# Eagle.net
KiCad netlist of a schematic drawn in EAGLE
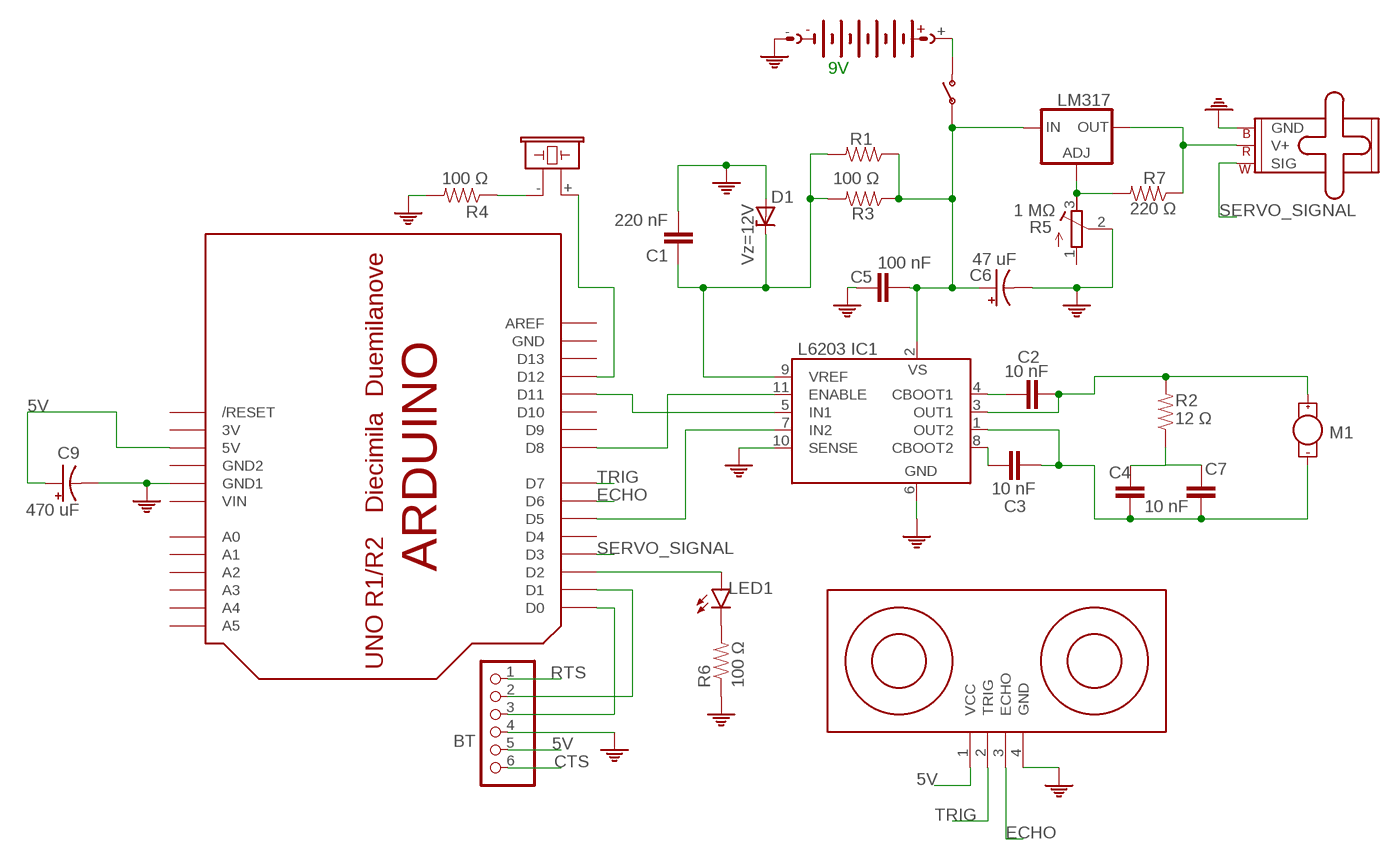
[diagram p0: schematic, sheet 1]

(export (version "E")
  (design (tool "Eeschema 10.0.6"))
  (components
    (comp (ref "9V")
      (value "9V")
      (footprint "eagle-import:AB9V")
      (libsource (lib "eagle-import") (part "AB9V"))
    )
    (comp (ref "BT")
      (value "PINHD-1X6")
      (footprint "eagle-import:1X06")
      (libsource (lib "eagle-import") (part "PINHD-1X6"))
    )
    (comp (ref "C1")
      (value "220 nF")
      (footprint "eagle-import:CAP-PTH-SMALLEZ")
      (libsource (lib "eagle-import") (part "CAPEZ"))
    )
    (comp (ref "C2")
      (value "10 nF")
      (footprint "eagle-import:CAP-PTH-SMALLEZ")
      (libsource (lib "eagle-import") (part "CAPEZ"))
    )
    (comp (ref "C3")
      (value "10 nF")
      (footprint "eagle-import:CAP-PTH-SMALLEZ")
      (libsource (lib "eagle-import") (part "CAPEZ"))
    )
    (comp (ref "C4")
      (value "10 nF")
      (footprint "eagle-import:CAP-PTH-SMALLEZ")
      (libsource (lib "eagle-import") (part "CAPEZ"))
    )
    (comp (ref "C5")
      (value "100 nF")
      (footprint "eagle-import:CAP-PTH-SMALLEZ")
      (libsource (lib "eagle-import") (part "CAPEZ"))
    )
    (comp (ref "C6")
      (value "47 uF")
      (footprint "eagle-import:E5-4")
      (libsource (lib "eagle-import") (part "CPOL-USE5-4"))
    )
    (comp (ref "C7")
      (value "10 nF")
      (footprint "eagle-import:CAP-PTH-SMALLEZ")
      (libsource (lib "eagle-import") (part "CAPEZ"))
    )
    (comp (ref "C9")
      (value "470 uF")
      (footprint "eagle-import:B45181A")
      (libsource (lib "eagle-import") (part "resistor_CPOL-USB45181A"))
    )
    (comp (ref "D1")
      (value "Vz=12V")
      (footprint "eagle-import:C1702-15")
      (libsource (lib "eagle-import") (part "ZENER-DIODEC1702-15"))
    )
    (comp (ref "IC1")
      (value "L6203")
      (footprint "eagle-import:MULTIWATT-11")
      (libsource (lib "eagle-import") (part "L6203"))
    )
    (comp (ref "LED1")
      (value "LED1")
      (footprint "eagle-import:LED3MM-NS")
      (libsource (lib "eagle-import") (part "LED-3MM-NO_SILK"))
    )
    (comp (ref "LM317")
      (value "LM317TS")
      (footprint "eagle-import:317TS")
      (libsource (lib "eagle-import") (part "LM317TS"))
    )
    (comp (ref "M1")
      (value "MOTOR10MM")
      (footprint "eagle-import:VIBE-MOTOR-10MM")
      (libsource (lib "eagle-import") (part "MOTOR10MM"))
    )
    (comp (ref "M2")
      (value "SMALL_SERVO")
      (footprint "eagle-import:1X03")
      (libsource (lib "eagle-import") (part "SMALL_SERVO"))
    )
    (comp (ref "R1")
      (value "100 Ω")
      (footprint "eagle-import:AXIAL-0.3EZ")
      (libsource (lib "eagle-import") (part "RESISTOREZ"))
    )
    (comp (ref "R2")
      (value "12 Ω")
      (footprint "eagle-import:AXIAL-0.3EZ")
      (libsource (lib "eagle-import") (part "RESISTOREZ"))
    )
    (comp (ref "R3")
      (value "100 Ω")
      (footprint "eagle-import:AXIAL-0.3EZ")
      (libsource (lib "eagle-import") (part "RESISTOREZ"))
    )
    (comp (ref "R4")
      (value "100 Ω")
      (footprint "eagle-import:AXIAL-0.3EZ")
      (libsource (lib "eagle-import") (part "RESISTOREZ"))
    )
    (comp (ref "R5")
      (value "1 MΩ")
      (footprint "eagle-import:RTRIM3296W")
      (libsource (lib "eagle-import") (part "R-TRIMM3296W"))
    )
    (comp (ref "R6")
      (value "100 Ω")
      (footprint "eagle-import:AXIAL-0.3EZ")
      (libsource (lib "eagle-import") (part "RESISTOREZ"))
    )
    (comp (ref "R7")
      (value "220 Ω")
      (footprint "eagle-import:AXIAL-0.3EZ")
      (libsource (lib "eagle-import") (part "RESISTOREZ"))
    )
    (comp (ref "SG1")
      (value "F/CM04P")
      (footprint "eagle-import:F_CM04P")
      (libsource (lib "eagle-import") (part "F/CM04P"))
    )
    (comp (ref "U$1")
      (value "ARDUINOUNO")
      (footprint "eagle-import:ARDUINO")
      (libsource (lib "eagle-import") (part "ARDUINOUNO"))
    )
    (comp (ref "U$2")
      (value "ULTRASONIC-HC-SR04#V")
      (footprint "eagle-import:ULTRASONIC-HC-SR04#V")
      (libsource (lib "eagle-import") (part "ULTRASONIC-HC-SR04#V"))
    )
    (comp (ref "U$3")
      (value "SWITCH-SPST-2TV")
      (footprint "eagle-import:SWITCH-SPST-VERTICAL")
      (libsource (lib "eagle-import") (part "SWITCH-SPST-2TV"))
    )
  )
  (nets
    (net (code "1") (name "/3V") (class "Default")
      (node (ref "U$1") (pin "3V") (pinfunction "3V_3V") (pintype "power_in"))
    )
    (net (code "2") (name "/5V") (class "Default")
      (node (ref "BT") (pin "5") (pinfunction "5_5") (pintype "passive"))
      (node (ref "C9") (pin "+") (pinfunction "+_+") (pintype "passive"))
      (node (ref "U$1") (pin "5V") (pinfunction "5V_5V") (pintype "power_in"))
      (node (ref "U$2") (pin "1") (pinfunction "VCC_1") (pintype "power_in"))
    )
    (net (code "3") (name "/CTS") (class "Default")
      (node (ref "BT") (pin "6") (pinfunction "6_6") (pintype "passive"))
    )
    (net (code "4") (name "/ECHO") (class "Default")
      (node (ref "U$1") (pin "D6") (pinfunction "D6_D6") (pintype "bidirectional"))
      (node (ref "U$2") (pin "3") (pinfunction "ECHO_3") (pintype "output"))
    )
    (net (code "5") (name "/GND") (class "Default")
      (node (ref "U$1") (pin "GND") (pinfunction "GND_GND") (pintype "power_in"))
    )
    (net (code "6") (name "/GND2") (class "Default")
      (node (ref "U$1") (pin "GND2") (pinfunction "GND2_GND2") (pintype "power_in"))
    )
    (net (code "7") (name "/RTS") (class "Default")
      (node (ref "BT") (pin "1") (pinfunction "1_1") (pintype "passive"))
    )
    (net (code "8") (name "/SERVO_SIGNAL") (class "Default")
      (node (ref "U$1") (pin "D3") (pinfunction "D3_D3") (pintype "bidirectional"))
    )
    (net (code "9") (name "/TRIG") (class "Default")
      (node (ref "U$1") (pin "D7") (pinfunction "D7_D7") (pintype "bidirectional"))
      (node (ref "U$2") (pin "2") (pinfunction "TRIG_2") (pintype "input"))
    )
    (net (code "10") (name "/VIN") (class "Default")
      (node (ref "U$1") (pin "VIN") (pinfunction "VIN_VIN") (pintype "power_in"))
    )
    (net (code "11") (name "Net-(BT-Pad2)") (class "Default")
      (node (ref "BT") (pin "2") (pinfunction "2_2") (pintype "passive"))
      (node (ref "U$1") (pin "D1") (pinfunction "D1_D1") (pintype "bidirectional"))
    )
    (net (code "12") (name "Net-(BT-Pad3)") (class "Default")
      (node (ref "BT") (pin "3") (pinfunction "3_3") (pintype "passive"))
      (node (ref "U$1") (pin "D0") (pinfunction "D0_D0") (pintype "bidirectional"))
    )
    (net (code "13") (name "Net-(IC1-CBOOT1)") (class "Default")
      (node (ref "C2") (pin "1") (pinfunction "1_1") (pintype "passive"))
      (node (ref "IC1") (pin "4") (pinfunction "CBOOT1_4") (pintype "input"))
    )
    (net (code "14") (name "Net-(IC1-CBOOT2)") (class "Default")
      (node (ref "C3") (pin "2") (pinfunction "2_2") (pintype "passive"))
      (node (ref "IC1") (pin "8") (pinfunction "CBOOT2_8") (pintype "input"))
    )
    (net (code "15") (name "Net-(IC1-ENABLE)") (class "Default")
      (node (ref "IC1") (pin "11") (pinfunction "ENABLE_11") (pintype "input"))
      (node (ref "U$1") (pin "D8") (pinfunction "D8_D8") (pintype "bidirectional"))
    )
    (net (code "16") (name "Net-(IC1-IN1)") (class "Default")
      (node (ref "IC1") (pin "5") (pinfunction "IN1_5") (pintype "input"))
      (node (ref "U$1") (pin "D11") (pinfunction "D11_D11") (pintype "bidirectional"))
    )
    (net (code "17") (name "Net-(IC1-IN2)") (class "Default")
      (node (ref "IC1") (pin "7") (pinfunction "IN2_7") (pintype "input"))
      (node (ref "U$1") (pin "D5") (pinfunction "D5_D5") (pintype "bidirectional"))
    )
    (net (code "18") (name "Net-(IC1-OUT1)") (class "Default")
      (node (ref "C2") (pin "2") (pinfunction "2_2") (pintype "passive"))
      (node (ref "IC1") (pin "3") (pinfunction "OUT1_3") (pintype "output"))
      (node (ref "M1") (pin "+") (pinfunction "+_+") (pintype "bidirectional"))
      (node (ref "R2") (pin "P$2") (pinfunction "2_P$2") (pintype "passive"))
    )
    (net (code "19") (name "Net-(IC1-OUT2)") (class "Default")
      (node (ref "C3") (pin "1") (pinfunction "1_1") (pintype "passive"))
      (node (ref "C4") (pin "2") (pinfunction "2_2") (pintype "passive"))
      (node (ref "C7") (pin "2") (pinfunction "2_2") (pintype "passive"))
      (node (ref "IC1") (pin "1") (pinfunction "OUT2_1") (pintype "output"))
      (node (ref "M1") (pin "-") (pinfunction "-_-") (pintype "bidirectional"))
    )
    (net (code "20") (name "Net-(IC1-VREF)") (class "Default")
      (node (ref "C1") (pin "1") (pinfunction "1_1") (pintype "passive"))
      (node (ref "D1") (pin "C") (pinfunction "C_C") (pintype "passive"))
      (node (ref "IC1") (pin "9") (pinfunction "VREF_9") (pintype "input"))
      (node (ref "R1") (pin "P$2") (pinfunction "2_P$2") (pintype "passive"))
      (node (ref "R3") (pin "P$2") (pinfunction "2_P$2") (pintype "passive"))
    )
    (net (code "21") (name "Net-(IC1-VS)") (class "Default")
      (node (ref "C5") (pin "2") (pinfunction "2_2") (pintype "passive"))
      (node (ref "C6") (pin "+") (pinfunction "+_+") (pintype "passive"))
      (node (ref "IC1") (pin "2") (pinfunction "VS_2") (pintype "power_in"))
      (node (ref "LM317") (pin "3") (pinfunction "IN_3") (pintype "input"))
      (node (ref "R1") (pin "P$1") (pinfunction "1_P$1") (pintype "passive"))
      (node (ref "R3") (pin "P$1") (pinfunction "1_P$1") (pintype "passive"))
      (node (ref "U$3") (pin "2") (pinfunction "P_2") (pintype "passive"))
    )
    (net (code "22") (name "Net-(LED1-C)") (class "Default")
      (node (ref "LED1") (pin "K") (pinfunction "C_K") (pintype "passive"))
      (node (ref "R6") (pin "P$2") (pinfunction "2_P$2") (pintype "passive"))
    )
    (net (code "23") (name "Net-(LED1-PadA)") (class "Default")
      (node (ref "LED1") (pin "A") (pinfunction "A_A") (pintype "passive"))
      (node (ref "U$1") (pin "D2") (pinfunction "D2_D2") (pintype "bidirectional"))
    )
    (net (code "24") (name "Net-(LM317-ADJ)") (class "Default")
      (node (ref "LM317") (pin "1") (pinfunction "ADJ_1") (pintype "input"))
      (node (ref "R5") (pin "3") (pinfunction "E_3") (pintype "passive"))
      (node (ref "R7") (pin "P$2") (pinfunction "2_P$2") (pintype "passive"))
    )
    (net (code "25") (name "Net-(LM317-OUT)") (class "Default")
      (node (ref "LM317") (pin "2") (pinfunction "OUT_2") (pintype "passive"))
      (node (ref "M2") (pin "2") (pinfunction "V+_2") (pintype "bidirectional"))
      (node (ref "R7") (pin "P$1") (pinfunction "1_P$1") (pintype "passive"))
    )
    (net (code "26") (name "Net-(R2-1)") (class "Default")
      (node (ref "C4") (pin "1") (pinfunction "1_1") (pintype "passive"))
      (node (ref "C7") (pin "1") (pinfunction "1_1") (pintype "passive"))
      (node (ref "R2") (pin "P$1") (pinfunction "1_P$1") (pintype "passive"))
    )
    (net (code "27") (name "Net-(R4-1)") (class "Default")
      (node (ref "R4") (pin "P$1") (pinfunction "1_P$1") (pintype "passive"))
      (node (ref "SG1") (pin "-") (pinfunction "2_-") (pintype "passive"))
    )
    (net (code "28") (name "Net-(SG1-1)") (class "Default")
      (node (ref "SG1") (pin "+") (pinfunction "1_+") (pintype "passive"))
      (node (ref "U$1") (pin "D12") (pinfunction "D12_D12") (pintype "bidirectional"))
    )
    (net (code "29") (name "Net-(U$3-O)") (class "Default")
      (node (ref "9V") (pin "+") (pinfunction "+_+") (pintype "passive"))
      (node (ref "U$3") (pin "1") (pinfunction "O_1") (pintype "passive"))
    )
    (net (code "30") (name "PE") (class "Default")
      (node (ref "9V") (pin "-") (pinfunction "-_-") (pintype "passive"))
      (node (ref "BT") (pin "4") (pinfunction "4_4") (pintype "passive"))
      (node (ref "C1") (pin "2") (pinfunction "2_2") (pintype "passive"))
      (node (ref "C5") (pin "1") (pinfunction "1_1") (pintype "passive"))
      (node (ref "C6") (pin "-") (pinfunction "-_-") (pintype "passive"))
      (node (ref "C9") (pin "-") (pinfunction "-_-") (pintype "passive"))
      (node (ref "D1") (pin "A") (pinfunction "A_A") (pintype "passive"))
      (node (ref "IC1") (pin "10") (pinfunction "SENSE_10") (pintype "input"))
      (node (ref "IC1") (pin "6") (pinfunction "GND_6") (pintype "power_in"))
      (node (ref "M2") (pin "3") (pinfunction "GND_3") (pintype "bidirectional"))
      (node (ref "R4") (pin "P$2") (pinfunction "2_P$2") (pintype "passive"))
      (node (ref "R5") (pin "2") (pinfunction "S_2") (pintype "passive"))
      (node (ref "R6") (pin "P$1") (pinfunction "1_P$1") (pintype "passive"))
      (node (ref "U$1") (pin "GND1") (pinfunction "GND1_GND1") (pintype "power_in"))
      (node (ref "U$2") (pin "4") (pinfunction "GND_4") (pintype "power_in"))
    )
    (net (code "31") (name "unconnected-(M2-SIG-Pad1)") (class "Default")
      (node (ref "M2") (pin "1") (pinfunction "SIG_1") (pintype "bidirectional"))
    )
    (net (code "32") (name "unconnected-(R5-A-Pad1)") (class "Default")
      (node (ref "R5") (pin "1") (pinfunction "A_1") (pintype "passive"))
    )
    (net (code "33") (name "unconnected-(U$1-PadA0)") (class "Default")
      (node (ref "U$1") (pin "A0") (pinfunction "A0_A0") (pintype "bidirectional"))
    )
    (net (code "34") (name "unconnected-(U$1-PadA1)") (class "Default")
      (node (ref "U$1") (pin "A1") (pinfunction "A1_A1") (pintype "bidirectional"))
    )
    (net (code "35") (name "unconnected-(U$1-PadA2)") (class "Default")
      (node (ref "U$1") (pin "A2") (pinfunction "A2_A2") (pintype "bidirectional"))
    )
    (net (code "36") (name "unconnected-(U$1-PadA3)") (class "Default")
      (node (ref "U$1") (pin "A3") (pinfunction "A3_A3") (pintype "bidirectional"))
    )
    (net (code "37") (name "unconnected-(U$1-PadA4)") (class "Default")
      (node (ref "U$1") (pin "A4") (pinfunction "A4_A4") (pintype "bidirectional"))
    )
    (net (code "38") (name "unconnected-(U$1-PadA5)") (class "Default")
      (node (ref "U$1") (pin "A5") (pinfunction "A5_A5") (pintype "bidirectional"))
    )
    (net (code "39") (name "unconnected-(U$1-PadAREF)") (class "Default")
      (node (ref "U$1") (pin "AREF") (pinfunction "AREF_AREF") (pintype "bidirectional"))
    )
    (net (code "40") (name "unconnected-(U$1-PadD4)") (class "Default")
      (node (ref "U$1") (pin "D4") (pinfunction "D4_D4") (pintype "bidirectional"))
    )
    (net (code "41") (name "unconnected-(U$1-PadD9)") (class "Default")
      (node (ref "U$1") (pin "D9") (pinfunction "D9_D9") (pintype "bidirectional"))
    )
    (net (code "42") (name "unconnected-(U$1-PadD10)") (class "Default")
      (node (ref "U$1") (pin "D10") (pinfunction "D10_D10") (pintype "bidirectional"))
    )
    (net (code "43") (name "unconnected-(U$1-PadD13)") (class "Default")
      (node (ref "U$1") (pin "D13") (pinfunction "D13_D13") (pintype "bidirectional"))
    )
    (net (code "44") (name "unconnected-(U$1-{slash}RESET-PadRESET)") (class "Default")
      (node (ref "U$1") (pin "RESET") (pinfunction "/RESET_RESET") (pintype "bidirectional"))
    )
  )
)
